# 02_MCU.net
KiCad netlist of a schematic drawn in Altium Designer
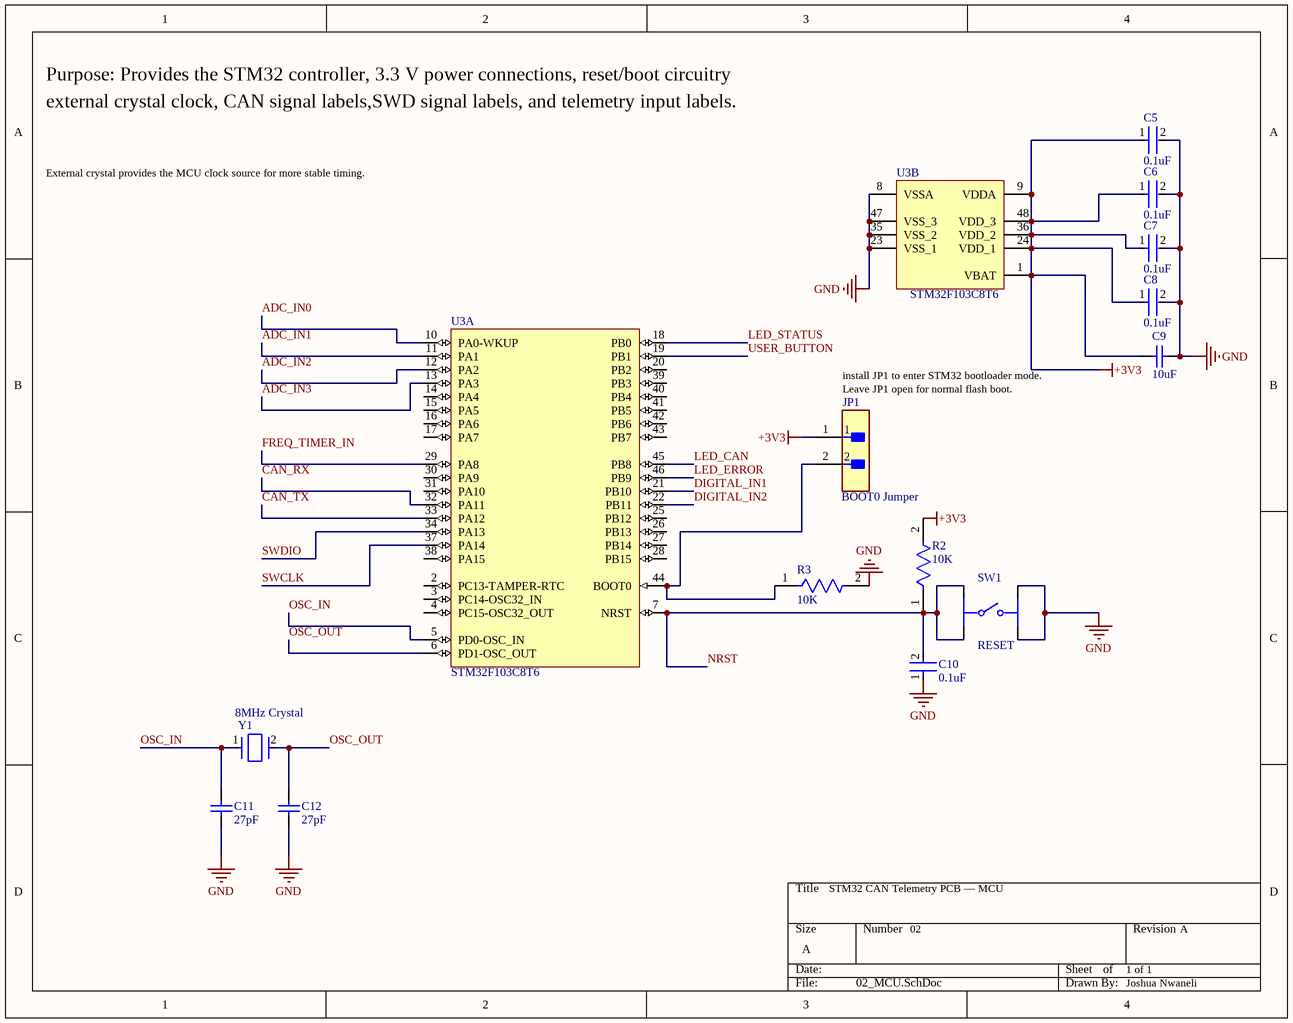
[diagram p0: 02_MCU.SchDoc]

(export (version "E")
  (design (tool "Eeschema 10.0.6"))
  (components
    (comp (ref "C5")
      (value "0.1uF")
      (footprint "FP-CC0805-EB-MFG")
      (description "CC0805KKX7RYBB104 Capacitor Ceramic 0.01uF 250V X7R 10% 0805 T/R")
      (fields (field (name "TOLERANCE") "10%"))
      (libsource (lib "Altium Content Vault") (part "b4654b650e69147ec39a6b967a45e02"))
    )
    (comp (ref "C6")
      (value "0.1uF")
      (footprint "FP-CC0805-EB-MFG")
      (description "CC0805KKX7RYBB104 Capacitor Ceramic 0.01uF 250V X7R 10% 0805 T/R")
      (fields (field (name "TOLERANCE") "10%"))
      (libsource (lib "Altium Content Vault") (part "b4654b650e69147ec39a6b967a45e02"))
    )
    (comp (ref "C7")
      (value "0.1uF")
      (footprint "FP-CC0805-EB-MFG")
      (description "CC0805KKX7RYBB104 Capacitor Ceramic 0.01uF 250V X7R 10% 0805 T/R")
      (fields (field (name "TOLERANCE") "10%"))
      (libsource (lib "Altium Content Vault") (part "b4654b650e69147ec39a6b967a45e02"))
    )
    (comp (ref "C8")
      (value "0.1uF")
      (footprint "FP-CC0805-EB-MFG")
      (description "CC0805KKX7RYBB104 Capacitor Ceramic 0.01uF 250V X7R 10% 0805 T/R")
      (fields (field (name "TOLERANCE") "10%"))
      (libsource (lib "Altium Content Vault") (part "b4654b650e69147ec39a6b967a45e02"))
    )
    (comp (ref "C9")
      (value "10uF")
      (footprint "CAPC2013X140X50ML20T25")
      (fields
        (field (name "MANUFACTURER") "AVX Interconnect / Elco")
        (field (name "PART NUMBER") "0805ZC106KAT2A")
      )
      (libsource (lib "Altium Content Vault") (part "CAP"))
    )
    (comp (ref "C10")
      (value "0.1uF")
      (footprint "FP-CC0805-EB-MFG")
      (description "CC0805KKX7RYBB104 Capacitor Ceramic 0.01uF 250V X7R 10% 0805 T/R")
      (fields (field (name "TOLERANCE") "10%"))
      (libsource (lib "Altium Content Vault") (part "b4654b650e69147ec39a6b967a45e02"))
    )
    (comp (ref "C11")
      (value "27pF")
      (footprint "CAPC0603X33X15ML03T05")
      (fields
        (field (name "MANUFACTURER") "AVX Interconnect / Elco")
        (field (name "PART NUMBER") "0201YA270JAT2A")
      )
      (libsource (lib "Altium Content Vault") (part "CAP"))
    )
    (comp (ref "C12")
      (value "27pF")
      (footprint "CAPC0603X33X15ML03T05")
      (fields
        (field (name "MANUFACTURER") "AVX Interconnect / Elco")
        (field (name "PART NUMBER") "0201YA270JAT2A")
      )
      (libsource (lib "Altium Content Vault") (part "CAP"))
    )
    (comp (ref "JP1")
      (value "BOOT0 Jumper")
      (footprint "FP-TSW-102-12-T-S-MFG")
      (description "CONN HEADER VERT 2POS 2.54MM")
      (libsource (lib "Altium Content Vault") (part "3bc925449376181038e59eaffc5286c"))
    )
    (comp (ref "R2")
      (value "10K")
      (footprint "FP-CRGP0805-IPC_C")
      (description "CRGP0805 10KΩ 0.33W ±100ppm/°C 1% 150V")
      (fields (field (name "MANUFACTURER PART NUMBER") "CRGP0805F10K"))
      (libsource (lib "Altium Content Vault") (part "1029c3af85768c4190bb7ad29bc67b5"))
    )
    (comp (ref "R3")
      (value "10K")
      (footprint "FP-CRGP0805-IPC_C")
      (description "CRGP0805 10KΩ 0.33W ±100ppm/°C 1% 150V")
      (fields (field (name "MANUFACTURER PART NUMBER") "CRGP0805F10K"))
      (libsource (lib "Altium Content Vault") (part "1029c3af85768c4190bb7ad29bc67b5"))
    )
    (comp (ref "SW1")
      (value "RESET")
      (footprint "FP-7914J-1-032-MFG")
      (description "Normally open reset pushbutton for STM32 NRST")
      (libsource (lib "Altium Content Vault") (part "31b61e1575766857d5d37af9ed38f2e"))
    )
    (comp (ref "U3")
      (value "STM32F103C8T6")
      (footprint "STM-LQFP48_L")
      (libsource (lib "Altium Content Vault") (part "MC-ARM-STM32F103X8_B-SQ48"))
    )
    (comp (ref "Y1")
      (value "8MHz Crystal")
      (footprint "FP-ABLS-MFG")
      (description "CRYSTAL 8.0000MHZ 18PF SMD")
      (fields (field (name "TOLERANCE") "20ppm"))
      (libsource (lib "Altium Content Vault") (part "c23a69dc6c9e2f18f2079038eb95dd1"))
    )
  )
  (nets
    (net (code "1") (name "+3V3") (class "Default")
      (node (ref "C5") (pin "1") (pinfunction "1_1") (pintype "passive"))
      (node (ref "C6") (pin "1") (pinfunction "1_1") (pintype "passive"))
      (node (ref "C7") (pin "1") (pinfunction "1_1") (pintype "passive"))
      (node (ref "C8") (pin "1") (pinfunction "1_1") (pintype "passive"))
      (node (ref "C9") (pin "2") (pinfunction "2_2") (pintype "passive"))
      (node (ref "JP1") (pin "1") (pinfunction "1_1") (pintype "passive"))
      (node (ref "R2") (pin "2") (pinfunction "2_2") (pintype "passive"))
      (node (ref "U3") (pin "1") (pinfunction "VBAT_1") (pintype "power_in"))
      (node (ref "U3") (pin "24") (pinfunction "VDD_1_24") (pintype "power_in"))
      (node (ref "U3") (pin "36") (pinfunction "VDD_2_36") (pintype "power_in"))
      (node (ref "U3") (pin "48") (pinfunction "VDD_3_48") (pintype "power_in"))
      (node (ref "U3") (pin "9") (pinfunction "VDDA_9") (pintype "power_in"))
    )
    (net (code "2") (name "/ADC_IN0") (class "Default")
      (node (ref "U3") (pin "10") (pinfunction "PA0-WKUP_10") (pintype "bidirectional"))
    )
    (net (code "3") (name "/ADC_IN1") (class "Default")
      (node (ref "U3") (pin "11") (pinfunction "PA1_11") (pintype "bidirectional"))
    )
    (net (code "4") (name "/ADC_IN2") (class "Default")
      (node (ref "U3") (pin "12") (pinfunction "PA2_12") (pintype "bidirectional"))
    )
    (net (code "5") (name "/ADC_IN3") (class "Default")
      (node (ref "U3") (pin "13") (pinfunction "PA3_13") (pintype "bidirectional"))
    )
    (net (code "6") (name "/CAN_RX") (class "Default")
      (node (ref "U3") (pin "32") (pinfunction "PA11_32") (pintype "bidirectional"))
    )
    (net (code "7") (name "/CAN_TX") (class "Default")
      (node (ref "U3") (pin "33") (pinfunction "PA12_33") (pintype "bidirectional"))
    )
    (net (code "8") (name "/DIGITAL_IN1") (class "Default")
      (node (ref "U3") (pin "21") (pinfunction "PB10_21") (pintype "bidirectional"))
    )
    (net (code "9") (name "/DIGITAL_IN2") (class "Default")
      (node (ref "U3") (pin "22") (pinfunction "PB11_22") (pintype "bidirectional"))
    )
    (net (code "10") (name "/FREQ_TIMER_IN") (class "Default")
      (node (ref "U3") (pin "29") (pinfunction "PA8_29") (pintype "bidirectional"))
    )
    (net (code "11") (name "/LED_CAN") (class "Default")
      (node (ref "U3") (pin "45") (pinfunction "PB8_45") (pintype "bidirectional"))
    )
    (net (code "12") (name "/LED_ERROR") (class "Default")
      (node (ref "U3") (pin "46") (pinfunction "PB9_46") (pintype "bidirectional"))
    )
    (net (code "13") (name "/LED_STATUS") (class "Default")
      (node (ref "U3") (pin "18") (pinfunction "PB0_18") (pintype "bidirectional"))
    )
    (net (code "14") (name "/NRST") (class "Default")
      (node (ref "C10") (pin "2") (pinfunction "2_2") (pintype "passive"))
      (node (ref "R2") (pin "1") (pinfunction "1_1") (pintype "passive"))
      (node (ref "SW1") (pin "1_1-") (pinfunction "1_1-_1_1-") (pintype "passive"))
      (node (ref "SW1") (pin "2_1-") (pinfunction "2_1-_2_1-") (pintype "passive"))
      (node (ref "U3") (pin "7") (pinfunction "NRST_7") (pintype "bidirectional"))
    )
    (net (code "15") (name "/OSC_IN") (class "Default")
      (node (ref "C11") (pin "2") (pinfunction "2_2") (pintype "passive"))
      (node (ref "U3") (pin "5") (pinfunction "PD0-OSC_IN_5") (pintype "bidirectional"))
      (node (ref "Y1") (pin "1") (pinfunction "1_1") (pintype "passive"))
    )
    (net (code "16") (name "/OSC_OUT") (class "Default")
      (node (ref "C12") (pin "2") (pinfunction "2_2") (pintype "passive"))
      (node (ref "U3") (pin "6") (pinfunction "PD1-OSC_OUT_6") (pintype "bidirectional"))
      (node (ref "Y1") (pin "2") (pinfunction "2_2") (pintype "passive"))
    )
    (net (code "17") (name "/SWCLK") (class "Default")
      (node (ref "U3") (pin "37") (pinfunction "PA14_37") (pintype "bidirectional"))
    )
    (net (code "18") (name "/SWDIO") (class "Default")
      (node (ref "U3") (pin "34") (pinfunction "PA13_34") (pintype "bidirectional"))
    )
    (net (code "19") (name "/USER_BUTTON") (class "Default")
      (node (ref "U3") (pin "19") (pinfunction "PB1_19") (pintype "bidirectional"))
    )
    (net (code "20") (name "GND") (class "Default")
      (node (ref "C10") (pin "1") (pinfunction "1_1") (pintype "passive"))
      (node (ref "C11") (pin "1") (pinfunction "1_1") (pintype "passive"))
      (node (ref "C12") (pin "1") (pinfunction "1_1") (pintype "passive"))
      (node (ref "C5") (pin "2") (pinfunction "2_2") (pintype "passive"))
      (node (ref "C6") (pin "2") (pinfunction "2_2") (pintype "passive"))
      (node (ref "C7") (pin "2") (pinfunction "2_2") (pintype "passive"))
      (node (ref "C8") (pin "2") (pinfunction "2_2") (pintype "passive"))
      (node (ref "C9") (pin "1") (pinfunction "1_1") (pintype "passive"))
      (node (ref "R3") (pin "2") (pinfunction "2_2") (pintype "passive"))
      (node (ref "SW1") (pin "1_2+") (pinfunction "1_2+_1_2+") (pintype "passive"))
      (node (ref "SW1") (pin "2_2+") (pinfunction "2_2+_2_2+") (pintype "passive"))
      (node (ref "U3") (pin "23") (pinfunction "VSS_1_23") (pintype "power_in"))
      (node (ref "U3") (pin "35") (pinfunction "VSS_2_35") (pintype "power_in"))
      (node (ref "U3") (pin "47") (pinfunction "VSS_3_47") (pintype "power_in"))
      (node (ref "U3") (pin "8") (pinfunction "VSSA_8") (pintype "power_in"))
    )
    (net (code "21") (name "Net-(U3A-BOOT0)") (class "Default")
      (node (ref "JP1") (pin "2") (pinfunction "2_2") (pintype "passive"))
      (node (ref "R3") (pin "1") (pinfunction "1_1") (pintype "passive"))
      (node (ref "U3") (pin "44") (pinfunction "BOOT0_44") (pintype "input"))
    )
    (net (code "22") (name "unconnected-(U3A-PA4-Pad14)") (class "Default")
      (node (ref "U3") (pin "14") (pinfunction "PA4_14") (pintype "bidirectional"))
    )
    (net (code "23") (name "unconnected-(U3A-PA5-Pad15)") (class "Default")
      (node (ref "U3") (pin "15") (pinfunction "PA5_15") (pintype "bidirectional"))
    )
    (net (code "24") (name "unconnected-(U3A-PA6-Pad16)") (class "Default")
      (node (ref "U3") (pin "16") (pinfunction "PA6_16") (pintype "bidirectional"))
    )
    (net (code "25") (name "unconnected-(U3A-PA7-Pad17)") (class "Default")
      (node (ref "U3") (pin "17") (pinfunction "PA7_17") (pintype "bidirectional"))
    )
    (net (code "26") (name "unconnected-(U3A-PA9-Pad30)") (class "Default")
      (node (ref "U3") (pin "30") (pinfunction "PA9_30") (pintype "bidirectional"))
    )
    (net (code "27") (name "unconnected-(U3A-PA10-Pad31)") (class "Default")
      (node (ref "U3") (pin "31") (pinfunction "PA10_31") (pintype "bidirectional"))
    )
    (net (code "28") (name "unconnected-(U3A-PA15-Pad38)") (class "Default")
      (node (ref "U3") (pin "38") (pinfunction "PA15_38") (pintype "bidirectional"))
    )
    (net (code "29") (name "unconnected-(U3A-PB2-Pad20)") (class "Default")
      (node (ref "U3") (pin "20") (pinfunction "PB2_20") (pintype "bidirectional"))
    )
    (net (code "30") (name "unconnected-(U3A-PB3-Pad39)") (class "Default")
      (node (ref "U3") (pin "39") (pinfunction "PB3_39") (pintype "bidirectional"))
    )
    (net (code "31") (name "unconnected-(U3A-PB4-Pad40)") (class "Default")
      (node (ref "U3") (pin "40") (pinfunction "PB4_40") (pintype "bidirectional"))
    )
    (net (code "32") (name "unconnected-(U3A-PB5-Pad41)") (class "Default")
      (node (ref "U3") (pin "41") (pinfunction "PB5_41") (pintype "bidirectional"))
    )
    (net (code "33") (name "unconnected-(U3A-PB6-Pad42)") (class "Default")
      (node (ref "U3") (pin "42") (pinfunction "PB6_42") (pintype "bidirectional"))
    )
    (net (code "34") (name "unconnected-(U3A-PB7-Pad43)") (class "Default")
      (node (ref "U3") (pin "43") (pinfunction "PB7_43") (pintype "bidirectional"))
    )
    (net (code "35") (name "unconnected-(U3A-PB12-Pad25)") (class "Default")
      (node (ref "U3") (pin "25") (pinfunction "PB12_25") (pintype "bidirectional"))
    )
    (net (code "36") (name "unconnected-(U3A-PB13-Pad26)") (class "Default")
      (node (ref "U3") (pin "26") (pinfunction "PB13_26") (pintype "bidirectional"))
    )
    (net (code "37") (name "unconnected-(U3A-PB14-Pad27)") (class "Default")
      (node (ref "U3") (pin "27") (pinfunction "PB14_27") (pintype "bidirectional"))
    )
    (net (code "38") (name "unconnected-(U3A-PB15-Pad28)") (class "Default")
      (node (ref "U3") (pin "28") (pinfunction "PB15_28") (pintype "bidirectional"))
    )
    (net (code "39") (name "unconnected-(U3A-PC13-TAMPER-RTC-Pad2)") (class "Default")
      (node (ref "U3") (pin "2") (pinfunction "PC13-TAMPER-RTC_2") (pintype "bidirectional"))
    )
    (net (code "40") (name "unconnected-(U3A-PC14-OSC32_IN-Pad3)") (class "Default")
      (node (ref "U3") (pin "3") (pinfunction "PC14-OSC32_IN_3") (pintype "bidirectional"))
    )
    (net (code "41") (name "unconnected-(U3A-PC15-OSC32_OUT-Pad4)") (class "Default")
      (node (ref "U3") (pin "4") (pinfunction "PC15-OSC32_OUT_4") (pintype "bidirectional"))
    )
  )
)
